# ST_LINK_V3E.net
KiCad netlist of a schematic drawn in Altium Designer
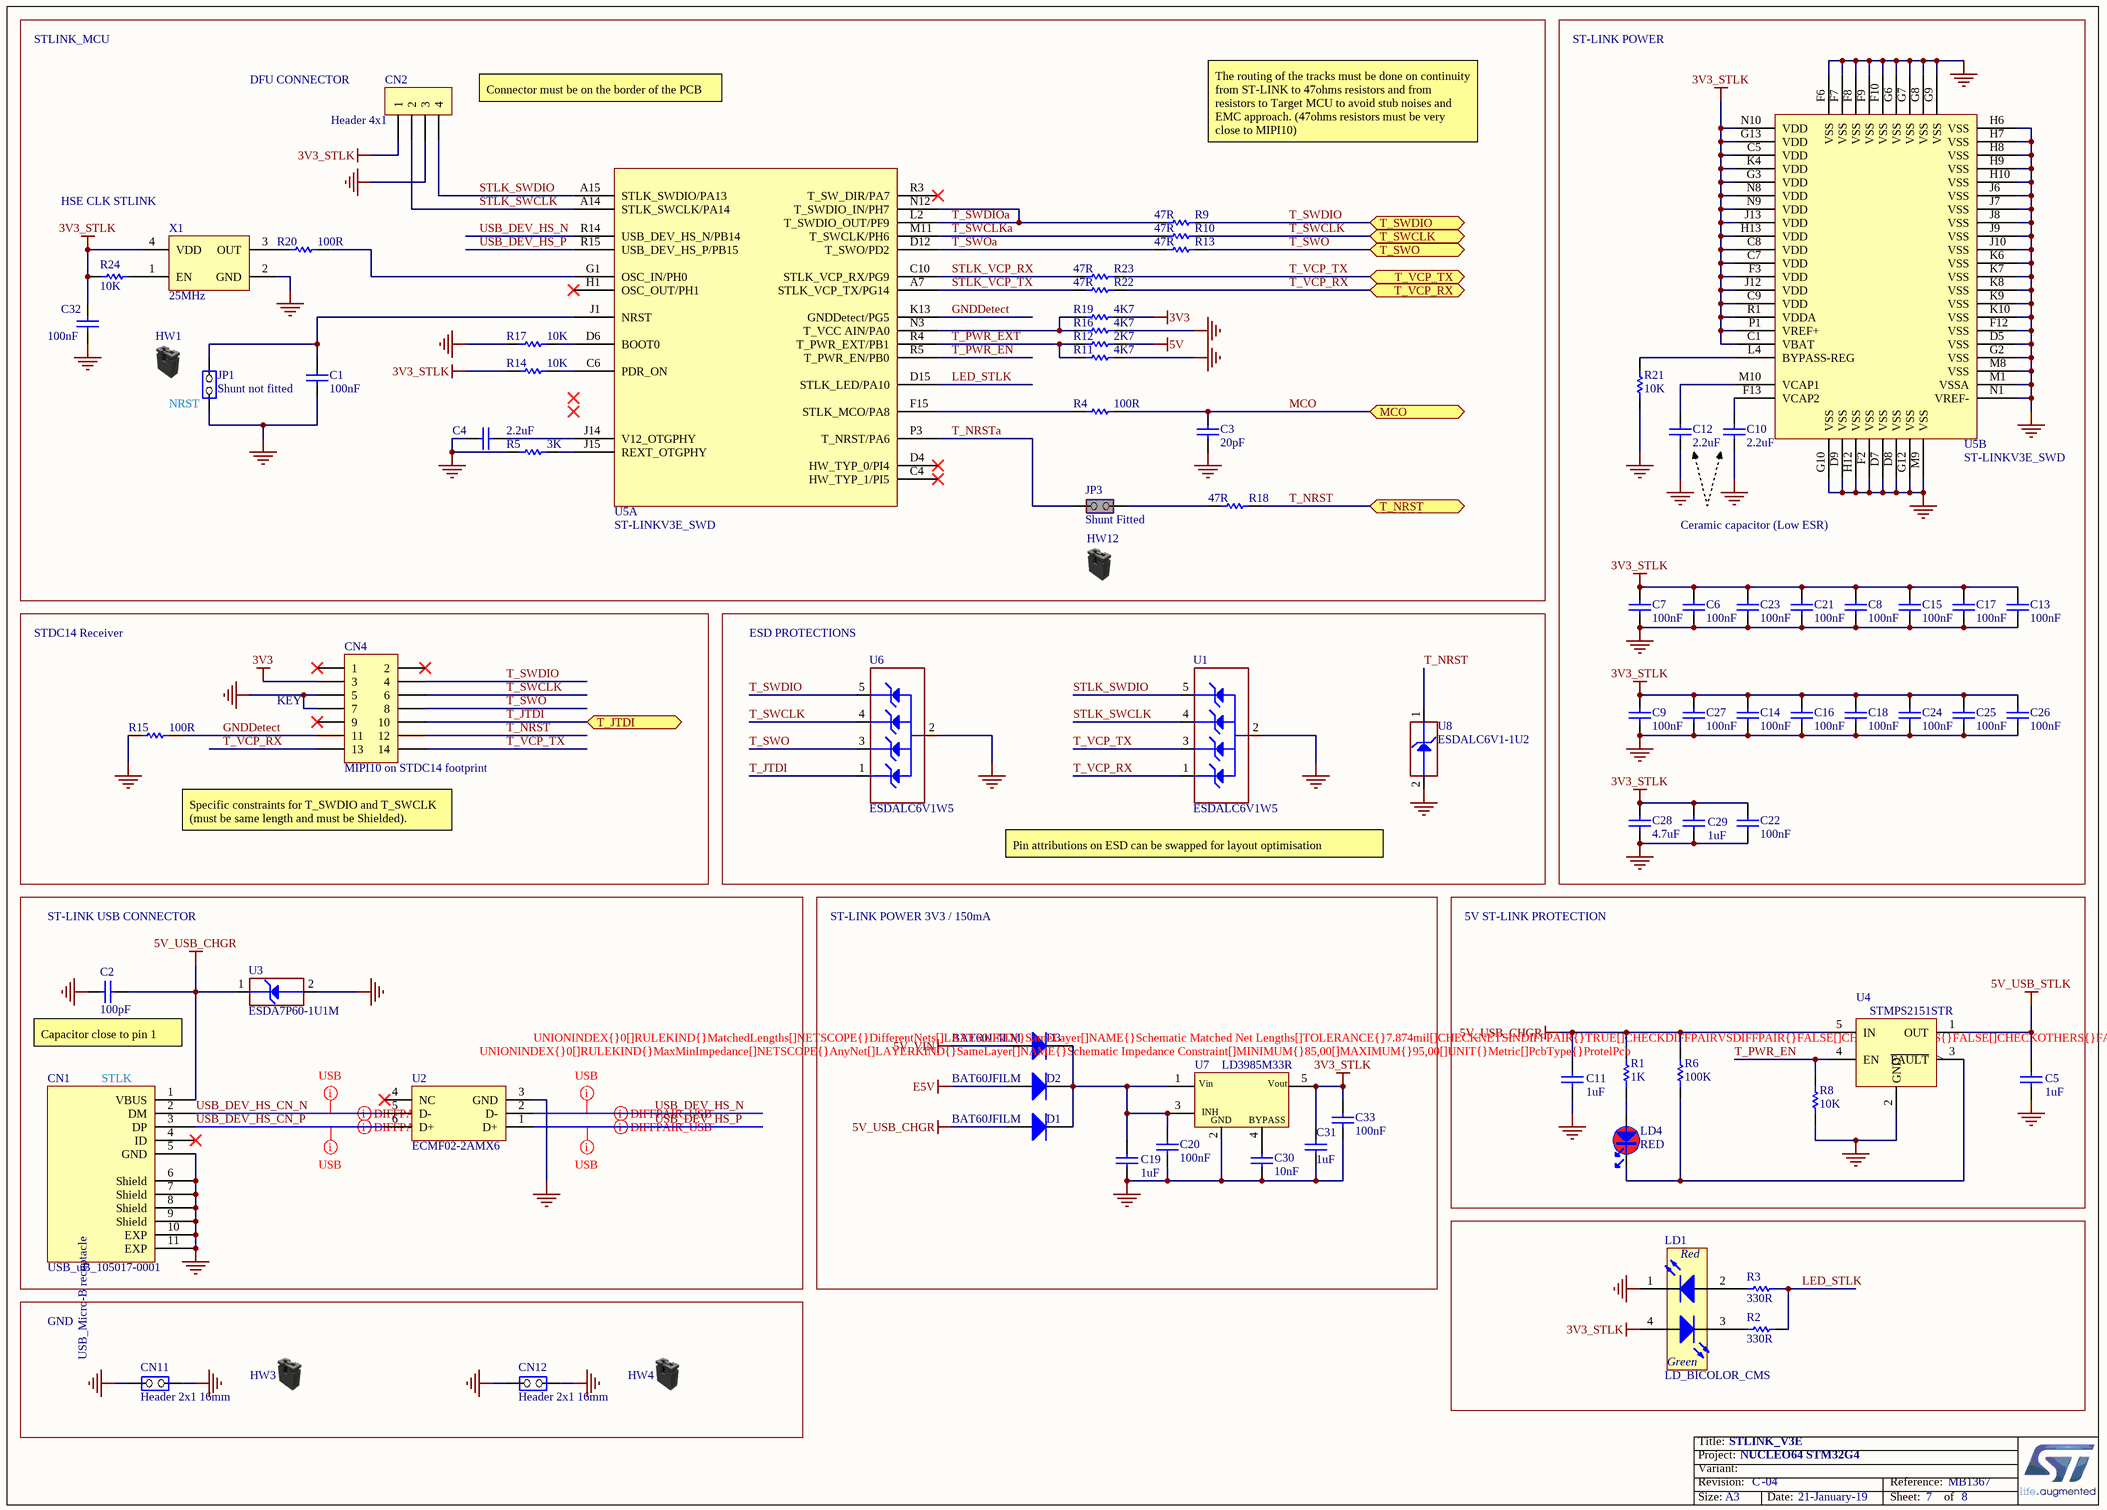
[diagram p0: ST_LINK_V3E.SchDoc]

(export (version "E")
  (design (tool "Eeschema 10.0.6"))
  (components
    (comp (ref "C1")
      (value "100nF")
      (footprint "C0402")
      (description "Capacitor, MLCC, 100nF, 16V, X7R, 10%, 0402, T=0,5mm")
      (fields
        (field (name "INTERNAL_PART_NUMBER") "MCD-00102")
        (field (name "MANUFACTURER_PART_NUMBER") "CC0402KRX7R7BB104")
      )
      (libsource (lib "MCD_PARTS_database") (part "Capacitor"))
    )
    (comp (ref "C2")
      (value "100pF")
      (footprint "C0402")
      (description "Capacitor, MLCC, 100pF, 50V, NPO, 5%, 0402, T=0,5mm")
      (fields
        (field (name "INTERNAL_PART_NUMBER") "MCD-00205")
        (field (name "MANUFACTURER_PART_NUMBER") "CC0402JRNPO9BN101")
      )
      (libsource (lib "MCD_PARTS_database") (part "Capacitor"))
    )
    (comp (ref "C3")
      (value "20pF")
      (footprint "C0402")
      (description "Capacitor, MLCC, 20pF, 50V, NPO, 5%, 0402, T=0,5mm")
      (fields
        (field (name "INTERNAL_PART_NUMBER") "MCD-00016")
        (field (name "MANUFACTURER_PART_NUMBER") "CC0402JRNPO9BN200")
      )
      (libsource (lib "MCD_PARTS_database") (part "Capacitor"))
    )
    (comp (ref "C4")
      (value "2.2uF")
      (footprint "C0603")
      (description "Capacitor, MLCC, 2.2uF, 10V, X5R, 10%, 0603, T=0,8mm")
      (fields
        (field (name "INTERNAL_PART_NUMBER") "MCD-00012")
        (field (name "MANUFACTURER_PART_NUMBER") "CC0603KRX5R6BB225")
      )
      (libsource (lib "MCD_PARTS_database") (part "Capacitor"))
    )
    (comp (ref "C5")
      (value "1uF")
      (footprint "C0603")
      (description "Capacitor, MLCC, 1uF, 16V, X5R, 10%, 0603, T=0,8mm")
      (fields
        (field (name "INTERNAL_PART_NUMBER") "MCD-00010")
        (field (name "MANUFACTURER_PART_NUMBER") "CC0603KRX5R7BB105")
      )
      (libsource (lib "MCD_PARTS_database") (part "Capacitor"))
    )
    (comp (ref "C6")
      (value "100nF")
      (footprint "C0402")
      (description "Capacitor, MLCC, 100nF, 16V, X7R, 10%, 0402, T=0,5mm")
      (fields
        (field (name "INTERNAL_PART_NUMBER") "MCD-00102")
        (field (name "MANUFACTURER_PART_NUMBER") "CC0402KRX7R7BB104")
      )
      (libsource (lib "MCD_PARTS_database") (part "Capacitor"))
    )
    (comp (ref "C7")
      (value "100nF")
      (footprint "C0402")
      (description "Capacitor, MLCC, 100nF, 16V, X7R, 10%, 0402, T=0,5mm")
      (fields
        (field (name "INTERNAL_PART_NUMBER") "MCD-00102")
        (field (name "MANUFACTURER_PART_NUMBER") "CC0402KRX7R7BB104")
      )
      (libsource (lib "MCD_PARTS_database") (part "Capacitor"))
    )
    (comp (ref "C8")
      (value "100nF")
      (footprint "C0402")
      (description "Capacitor, MLCC, 100nF, 16V, X7R, 10%, 0402, T=0,5mm")
      (fields
        (field (name "INTERNAL_PART_NUMBER") "MCD-00102")
        (field (name "MANUFACTURER_PART_NUMBER") "CC0402KRX7R7BB104")
      )
      (libsource (lib "MCD_PARTS_database") (part "Capacitor"))
    )
    (comp (ref "C9")
      (value "100nF")
      (footprint "C0402")
      (description "Capacitor, MLCC, 100nF, 16V, X7R, 10%, 0402, T=0,5mm")
      (fields
        (field (name "INTERNAL_PART_NUMBER") "MCD-00102")
        (field (name "MANUFACTURER_PART_NUMBER") "CC0402KRX7R7BB104")
      )
      (libsource (lib "MCD_PARTS_database") (part "Capacitor"))
    )
    (comp (ref "C10")
      (value "2.2uF")
      (footprint "C1206_H1P15")
      (description "Capacitor, MLCC, 2.2uF, 16V, X7R, 10%, 1206, T=1,15mm")
      (fields
        (field (name "INTERNAL_PART_NUMBER") "MCD-00008")
        (field (name "MANUFACTURER_PART_NUMBER") "CC1206KKX7R7BB225")
      )
      (libsource (lib "MCD_PARTS_database") (part "Capacitor"))
    )
    (comp (ref "C11")
      (value "1uF")
      (footprint "C0603")
      (description "Capacitor, MLCC, 1uF, 16V, X5R, 10%, 0603, T=0,8mm")
      (fields
        (field (name "INTERNAL_PART_NUMBER") "MCD-00010")
        (field (name "MANUFACTURER_PART_NUMBER") "CC0603KRX5R7BB105")
      )
      (libsource (lib "MCD_PARTS_database") (part "Capacitor"))
    )
    (comp (ref "C12")
      (value "2.2uF")
      (footprint "C1206_H1P15")
      (description "Capacitor, MLCC, 2.2uF, 16V, X7R, 10%, 1206, T=1,15mm")
      (fields
        (field (name "INTERNAL_PART_NUMBER") "MCD-00008")
        (field (name "MANUFACTURER_PART_NUMBER") "CC1206KKX7R7BB225")
      )
      (libsource (lib "MCD_PARTS_database") (part "Capacitor"))
    )
    (comp (ref "C13")
      (value "100nF")
      (footprint "C0402")
      (description "Capacitor, MLCC, 100nF, 16V, X7R, 10%, 0402, T=0,5mm")
      (fields
        (field (name "INTERNAL_PART_NUMBER") "MCD-00102")
        (field (name "MANUFACTURER_PART_NUMBER") "CC0402KRX7R7BB104")
      )
      (libsource (lib "MCD_PARTS_database") (part "Capacitor"))
    )
    (comp (ref "C14")
      (value "100nF")
      (footprint "C0402")
      (description "Capacitor, MLCC, 100nF, 16V, X7R, 10%, 0402, T=0,5mm")
      (fields
        (field (name "INTERNAL_PART_NUMBER") "MCD-00102")
        (field (name "MANUFACTURER_PART_NUMBER") "CC0402KRX7R7BB104")
      )
      (libsource (lib "MCD_PARTS_database") (part "Capacitor"))
    )
    (comp (ref "C15")
      (value "100nF")
      (footprint "C0402")
      (description "Capacitor, MLCC, 100nF, 16V, X7R, 10%, 0402, T=0,5mm")
      (fields
        (field (name "INTERNAL_PART_NUMBER") "MCD-00102")
        (field (name "MANUFACTURER_PART_NUMBER") "CC0402KRX7R7BB104")
      )
      (libsource (lib "MCD_PARTS_database") (part "Capacitor"))
    )
    (comp (ref "C16")
      (value "100nF")
      (footprint "C0402")
      (description "Capacitor, MLCC, 100nF, 16V, X7R, 10%, 0402, T=0,5mm")
      (fields
        (field (name "INTERNAL_PART_NUMBER") "MCD-00102")
        (field (name "MANUFACTURER_PART_NUMBER") "CC0402KRX7R7BB104")
      )
      (libsource (lib "MCD_PARTS_database") (part "Capacitor"))
    )
    (comp (ref "C17")
      (value "100nF")
      (footprint "C0402")
      (description "Capacitor, MLCC, 100nF, 16V, X7R, 10%, 0402, T=0,5mm")
      (fields
        (field (name "INTERNAL_PART_NUMBER") "MCD-00102")
        (field (name "MANUFACTURER_PART_NUMBER") "CC0402KRX7R7BB104")
      )
      (libsource (lib "MCD_PARTS_database") (part "Capacitor"))
    )
    (comp (ref "C18")
      (value "100nF")
      (footprint "C0402")
      (description "Capacitor, MLCC, 100nF, 16V, X7R, 10%, 0402, T=0,5mm")
      (fields
        (field (name "INTERNAL_PART_NUMBER") "MCD-00102")
        (field (name "MANUFACTURER_PART_NUMBER") "CC0402KRX7R7BB104")
      )
      (libsource (lib "MCD_PARTS_database") (part "Capacitor"))
    )
    (comp (ref "C19")
      (value "1uF")
      (footprint "C0603")
      (description "Capacitor, MLCC, 1uF, 16V, X5R, 10%, 0603, T=0,8mm")
      (fields
        (field (name "INTERNAL_PART_NUMBER") "MCD-00010")
        (field (name "MANUFACTURER_PART_NUMBER") "CC0603KRX5R7BB105")
      )
      (libsource (lib "MCD_PARTS_database") (part "Capacitor"))
    )
    (comp (ref "C20")
      (value "100nF")
      (footprint "C0402")
      (description "Capacitor, MLCC, 100nF, 16V, X7R, 10%, 0402, T=0,5mm")
      (fields
        (field (name "INTERNAL_PART_NUMBER") "MCD-00102")
        (field (name "MANUFACTURER_PART_NUMBER") "CC0402KRX7R7BB104")
      )
      (libsource (lib "MCD_PARTS_database") (part "Capacitor"))
    )
    (comp (ref "C21")
      (value "100nF")
      (footprint "C0402")
      (description "Capacitor, MLCC, 100nF, 16V, X7R, 10%, 0402, T=0,5mm")
      (fields
        (field (name "INTERNAL_PART_NUMBER") "MCD-00102")
        (field (name "MANUFACTURER_PART_NUMBER") "CC0402KRX7R7BB104")
      )
      (libsource (lib "MCD_PARTS_database") (part "Capacitor"))
    )
    (comp (ref "C22")
      (value "100nF")
      (footprint "C0402")
      (description "Capacitor, MLCC, 100nF, 16V, X7R, 10%, 0402, T=0,5mm")
      (fields
        (field (name "INTERNAL_PART_NUMBER") "MCD-00102")
        (field (name "MANUFACTURER_PART_NUMBER") "CC0402KRX7R7BB104")
      )
      (libsource (lib "MCD_PARTS_database") (part "Capacitor"))
    )
    (comp (ref "C23")
      (value "100nF")
      (footprint "C0402")
      (description "Capacitor, MLCC, 100nF, 16V, X7R, 10%, 0402, T=0,5mm")
      (fields
        (field (name "INTERNAL_PART_NUMBER") "MCD-00102")
        (field (name "MANUFACTURER_PART_NUMBER") "CC0402KRX7R7BB104")
      )
      (libsource (lib "MCD_PARTS_database") (part "Capacitor"))
    )
    (comp (ref "C24")
      (value "100nF")
      (footprint "C0402")
      (description "Capacitor, MLCC, 100nF, 16V, X7R, 10%, 0402, T=0,5mm")
      (fields
        (field (name "INTERNAL_PART_NUMBER") "MCD-00102")
        (field (name "MANUFACTURER_PART_NUMBER") "CC0402KRX7R7BB104")
      )
      (libsource (lib "MCD_PARTS_database") (part "Capacitor"))
    )
    (comp (ref "C25")
      (value "100nF")
      (footprint "C0402")
      (description "Capacitor, MLCC, 100nF, 16V, X7R, 10%, 0402, T=0,5mm")
      (fields
        (field (name "INTERNAL_PART_NUMBER") "MCD-00102")
        (field (name "MANUFACTURER_PART_NUMBER") "CC0402KRX7R7BB104")
      )
      (libsource (lib "MCD_PARTS_database") (part "Capacitor"))
    )
    (comp (ref "C26")
      (value "100nF")
      (footprint "C0402")
      (description "Capacitor, MLCC, 100nF, 16V, X7R, 10%, 0402, T=0,5mm")
      (fields
        (field (name "INTERNAL_PART_NUMBER") "MCD-00102")
        (field (name "MANUFACTURER_PART_NUMBER") "CC0402KRX7R7BB104")
      )
      (libsource (lib "MCD_PARTS_database") (part "Capacitor"))
    )
    (comp (ref "C27")
      (value "100nF")
      (footprint "C0402")
      (description "Capacitor, MLCC, 100nF, 16V, X7R, 10%, 0402, T=0,5mm")
      (fields
        (field (name "INTERNAL_PART_NUMBER") "MCD-00102")
        (field (name "MANUFACTURER_PART_NUMBER") "CC0402KRX7R7BB104")
      )
      (libsource (lib "MCD_PARTS_database") (part "Capacitor"))
    )
    (comp (ref "C28")
      (value "4.7uF")
      (footprint "C0603")
      (description "Capacitor, MLCC, 4.7uF, 16V, X5R, 10%, 0603, T=0.8mm")
      (fields
        (field (name "INTERNAL_PART_NUMBER") "MCD-00009")
        (field (name "MANUFACTURER_PART_NUMBER") "CC0603KRX5R7BB475")
      )
      (libsource (lib "MCD_PARTS_database") (part "Capacitor"))
    )
    (comp (ref "C29")
      (value "1uF")
      (footprint "C0603")
      (description "Capacitor, MLCC, 1uF, 16V, X5R, 10%, 0603, T=0,8mm")
      (fields
        (field (name "INTERNAL_PART_NUMBER") "MCD-00010")
        (field (name "MANUFACTURER_PART_NUMBER") "CC0603KRX5R7BB105")
      )
      (libsource (lib "MCD_PARTS_database") (part "Capacitor"))
    )
    (comp (ref "C30")
      (value "10nF")
      (footprint "C0402")
      (description "Capacitor, MLCC, 10nF, 16V, X7R, 10%, 0402, T=0.5mm")
      (fields
        (field (name "INTERNAL_PART_NUMBER") "MCD-00011")
        (field (name "MANUFACTURER_PART_NUMBER") "CC0402KRX7R7BB103")
      )
      (libsource (lib "MCD_PARTS_database") (part "Capacitor"))
    )
    (comp (ref "C31")
      (value "1uF")
      (footprint "C0603")
      (description "Capacitor, MLCC, 1uF, 16V, X5R, 10%, 0603, T=0,8mm")
      (fields
        (field (name "INTERNAL_PART_NUMBER") "MCD-00010")
        (field (name "MANUFACTURER_PART_NUMBER") "CC0603KRX5R7BB105")
      )
      (libsource (lib "MCD_PARTS_database") (part "Capacitor"))
    )
    (comp (ref "C32")
      (value "100nF")
      (footprint "C0402")
      (description "Capacitor, MLCC, 100nF, 16V, X7R, 10%, 0402, T=0,5mm")
      (fields
        (field (name "INTERNAL_PART_NUMBER") "MCD-00102")
        (field (name "MANUFACTURER_PART_NUMBER") "CC0402KRX7R7BB104")
      )
      (libsource (lib "MCD_PARTS_database") (part "Capacitor"))
    )
    (comp (ref "C33")
      (value "100nF")
      (footprint "C0402")
      (description "Capacitor, MLCC, 100nF, 16V, X7R, 10%, 0402, T=0,5mm")
      (fields
        (field (name "INTERNAL_PART_NUMBER") "MCD-00102")
        (field (name "MANUFACTURER_PART_NUMBER") "CC0402KRX7R7BB104")
      )
      (libsource (lib "MCD_PARTS_database") (part "Capacitor"))
    )
    (comp (ref "CN1")
      (value "USB_uB_105017-0001")
      (footprint "CON_USBMICROB_MOLEX_105017-0001_H2P90")
      (description "USB-MICRO-B, 0.65mm, RA, SMT, Bottom Mount,")
      (fields
        (field (name "INTERNAL_PART_NUMBER") "MCD-00028")
        (field (name "MANUFACTURER_PART_NUMBER") "1050170001")
      )
      (libsource (lib "MCD_PARTS_database") (part "USB_uB_105017.0001"))
    )
    (comp (ref "CN2")
      (value "Header 4x1")
      (footprint "CON_SAMTEC_TSW-104-07-G-S")
      (description "Header, 4x1, 2,54mm, VR, TH, Height 5.84mm/2.54mm")
      (fields
        (field (name "INTERNAL_PART_NUMBER") "MCD-00029")
        (field (name "MANUFACTURER_PART_NUMBER") "TSW-104-07-x-S")
      )
      (libsource (lib "MCD_PARTS_database") (part "Header 4x1"))
    )
    (comp (ref "CN4")
      (value "MIPI10 on STDC14 footprint")
      (footprint "CON_STDC14_Receiver_MEDIUM_WITH_MIPI10_3D")
      (fields
        (field (name "INTERNAL_PART_NUMBER") "MCD-01226")
        (field (name "MANUFACTURER_PART_NUMBER") "FTSH-105-01-L-DV-K")
        (field (name "MANUFACTURER") "SAMTEC")
      )
      (libsource (lib "MCD_PARTS_database") (part "Header 7x2"))
    )
    (comp (ref "CN11")
      (value "Header 2x1 16mm")
      (footprint "CON_SAMTEC_TSW-102-09-X-S")
      (description "Header, 2x1, 2,54mm, VR, TH, Height 5.84mm/10.16mm")
      (fields
        (field (name "INTERNAL_PART_NUMBER") "MCD-00214")
        (field (name "MANUFACTURER_PART_NUMBER") "TSW-102-09-x-S")
      )
      (libsource (lib "MCD_PARTS_database") (part "Jumper_Header 2x1"))
    )
    (comp (ref "CN12")
      (value "Header 2x1 16mm")
      (footprint "CON_SAMTEC_TSW-102-09-X-S")
      (description "Header, 2x1, 2,54mm, VR, TH, Height 5.84mm/10.16mm")
      (fields
        (field (name "INTERNAL_PART_NUMBER") "MCD-00214")
        (field (name "MANUFACTURER_PART_NUMBER") "TSW-102-09-x-S")
      )
      (libsource (lib "MCD_PARTS_database") (part "Jumper_Header 2x1"))
    )
    (comp (ref "D1")
      (value "BAT60JFILM")
      (footprint "DIO_SOD323")
      (fields
        (field (name "INTERNAL_PART_NUMBER") "MCD-00034")
        (field (name "MANUFACTURER") "STMICROELECTRONICS")
      )
      (libsource (lib "MCD_PARTS_database") (part "BAT60JFILM"))
    )
    (comp (ref "D2")
      (value "BAT60JFILM")
      (footprint "DIO_SOD323")
      (fields
        (field (name "INTERNAL_PART_NUMBER") "MCD-00034")
        (field (name "MANUFACTURER") "STMICROELECTRONICS")
      )
      (libsource (lib "MCD_PARTS_database") (part "BAT60JFILM"))
    )
    (comp (ref "D3")
      (value "BAT60JFILM")
      (footprint "DIO_SOD323")
      (fields
        (field (name "INTERNAL_PART_NUMBER") "MCD-00034")
        (field (name "MANUFACTURER") "STMICROELECTRONICS")
      )
      (libsource (lib "MCD_PARTS_database") (part "BAT60JFILM"))
    )
    (comp (ref "HW1")
      (value "~")
      (description "SHUNT 2.54mm BLACK")
      (fields
        (field (name "INTERNAL_PART_NUMBER") "MCD-00043")
        (field (name "MANUFACTURER_PART_NUMBER") "SNT-100-BK-G")
      )
      (libsource (lib "MCD_PARTS_database") (part "Shunt Black 2.54mm"))
    )
    (comp (ref "HW3")
      (value "~")
      (description "SHUNT 2.54mm BLACK")
      (fields
        (field (name "INTERNAL_PART_NUMBER") "MCD-00043")
        (field (name "MANUFACTURER_PART_NUMBER") "SNT-100-BK-G")
      )
      (libsource (lib "MCD_PARTS_database") (part "Shunt Black 2.54mm"))
    )
    (comp (ref "HW4")
      (value "~")
      (description "SHUNT 2.54mm BLACK")
      (fields
        (field (name "INTERNAL_PART_NUMBER") "MCD-00043")
        (field (name "MANUFACTURER_PART_NUMBER") "SNT-100-BK-G")
      )
      (libsource (lib "MCD_PARTS_database") (part "Shunt Black 2.54mm"))
    )
    (comp (ref "HW12")
      (value "~")
      (description "SHUNT 2.54mm BLACK")
      (fields
        (field (name "INTERNAL_PART_NUMBER") "MCD-00043")
        (field (name "MANUFACTURER_PART_NUMBER") "SNT-100-BK-G")
      )
      (libsource (lib "MCD_PARTS_database") (part "Shunt Black 2.54mm"))
    )
    (comp (ref "JP1")
      (value "Shunt not fitted")
      (footprint "CON_SAMTEC_TSW-102-07-G-S")
      (description "Header, 2x1, 2,54mm, VR, TH, Height 5.84mm/2.54mm")
      (fields
        (field (name "INTERNAL_PART_NUMBER") "MCD-00045")
        (field (name "MANUFACTURER_PART_NUMBER") "TSW-102-07-x-S")
      )
      (libsource (lib "MCD_PARTS_database") (part "Jumper_Header 2x1"))
    )
    (comp (ref "JP3")
      (value "Shunt Fitted")
      (footprint "CON_SAMTEC_TSW-102-07-G-S")
      (description "Header, 2x1, 2,54mm, VR, TH, Height 5.84mm/2.54mm - Shunt Fitted by default")
      (fields
        (field (name "INTERNAL_PART_NUMBER") "MCD-00683")
        (field (name "MANUFACTURER_PART_NUMBER") "TSW-102-07-x-S")
      )
      (libsource (lib "MCD_PARTS_database") (part "Jumper_Header 2x1 Fitted"))
    )
    (comp (ref "LD1")
      (value "LD_BICOLOR_CMS")
      (footprint "LED_BI-GR_HSMF-A201-A00J1")
      (description "LED Bicolor")
      (fields
        (field (name "INTERNAL_PART_NUMBER") "MCD-00051")
        (field (name "MANUFACTURER_PART_NUMBER") "HSMF-A201-A00J1")
      )
      (libsource (lib "MCD_PARTS_database") (part "LD_BICOLOR_CMS"))
    )
    (comp (ref "LD4")
      (value "RED")
      (footprint "LED_0603_RED")
      (description "LED, Red, 0603")
      (fields
        (field (name "INTERNAL_PART_NUMBER") "MCD-00049")
        (field (name "MANUFACTURER_PART_NUMBER") "19-213-R6C-AP1Q2B/3T")
      )
      (libsource (lib "MCD_PARTS_database") (part "LED_red"))
    )
    (comp (ref "R1")
      (value "1K")
      (footprint "R0603")
      (description "Resistor,1K,0603,1%,1/10W")
      (fields
        (field (name "INTERNAL_PART_NUMBER") "MCD-00070")
        (field (name "MANUFACTURER_PART_NUMBER") "RC0603FR-071KL")
      )
      (libsource (lib "MCD_PARTS_database") (part "Resistor"))
    )
    (comp (ref "R2")
      (value "330R")
      (footprint "R0603")
      (description "Resistor,330R,0603,1%,1/10W")
      (fields
        (field (name "INTERNAL_PART_NUMBER") "MCD-00197")
        (field (name "MANUFACTURER_PART_NUMBER") "RC0603FR-07330RL")
      )
      (libsource (lib "MCD_PARTS_database") (part "Resistor"))
    )
    (comp (ref "R3")
      (value "330R")
      (footprint "R0603")
      (description "Resistor,330R,0603,1%,1/10W")
      (fields
        (field (name "INTERNAL_PART_NUMBER") "MCD-00197")
        (field (name "MANUFACTURER_PART_NUMBER") "RC0603FR-07330RL")
      )
      (libsource (lib "MCD_PARTS_database") (part "Resistor"))
    )
    (comp (ref "R4")
      (value "100R")
      (footprint "R0402")
      (description "Resistor,100R,0402,1%,1/16W")
      (fields
        (field (name "INTERNAL_PART_NUMBER") "MCD-00119")
        (field (name "MANUFACTURER_PART_NUMBER") "RC0402FR-07100RL")
      )
      (libsource (lib "MCD_PARTS_database") (part "Resistor"))
    )
    (comp (ref "R5")
      (value "3K")
      (footprint "R0402")
      (description "Resistor,3K,0402,1%,1/16W")
      (fields
        (field (name "INTERNAL_PART_NUMBER") "MCD-00185")
        (field (name "MANUFACTURER_PART_NUMBER") "RC0402FR-073KL")
      )
      (libsource (lib "MCD_PARTS_database") (part "Resistor"))
    )
    (comp (ref "R6")
      (value "100K")
      (footprint "R0603")
      (description "Resistor,100K,0603,1%,1/10W")
      (fields
        (field (name "INTERNAL_PART_NUMBER") "MCD-00223")
        (field (name "MANUFACTURER_PART_NUMBER") "RC0603FR-07100KL")
      )
      (libsource (lib "MCD_PARTS_database") (part "Resistor"))
    )
    (comp (ref "R8")
      (value "10K")
      (footprint "R0603")
      (description "Resistor,10K,0603,1%,1/10W")
      (fields
        (field (name "INTERNAL_PART_NUMBER") "MCD-00220")
        (field (name "MANUFACTURER_PART_NUMBER") "RC0603FR-0710KL")
      )
      (libsource (lib "MCD_PARTS_database") (part "Resistor"))
    )
    (comp (ref "R9")
      (value "47R")
      (footprint "R0402")
      (description "Resistor,47R,0402,1%,1/16W")
      (fields
        (field (name "INTERNAL_PART_NUMBER") "MCD-00481")
        (field (name "MANUFACTURER_PART_NUMBER") "RC0402FR-0747RL")
      )
      (libsource (lib "MCD_PARTS_database") (part "Resistor"))
    )
    (comp (ref "R10")
      (value "47R")
      (footprint "R0402")
      (description "Resistor,47R,0402,1%,1/16W")
      (fields
        (field (name "INTERNAL_PART_NUMBER") "MCD-00481")
        (field (name "MANUFACTURER_PART_NUMBER") "RC0402FR-0747RL")
      )
      (libsource (lib "MCD_PARTS_database") (part "Resistor"))
    )
    (comp (ref "R11")
      (value "4K7")
      (footprint "R0402")
      (description "Resistor,4K7,0402,1%,1/16W")
      (fields
        (field (name "INTERNAL_PART_NUMBER") "MCD-00065")
        (field (name "MANUFACTURER_PART_NUMBER") "RC0402FR-074K7L")
      )
      (libsource (lib "MCD_PARTS_database") (part "Resistor"))
    )
    (comp (ref "R12")
      (value "2K7")
      (footprint "R0402")
      (description "Resistor,2K7,0402,1%,1/16W")
      (fields
        (field (name "INTERNAL_PART_NUMBER") "MCD-00055")
        (field (name "MANUFACTURER_PART_NUMBER") "RC0402FR-072K7L")
      )
      (libsource (lib "MCD_PARTS_database") (part "Resistor"))
    )
    (comp (ref "R13")
      (value "47R")
      (footprint "R0402")
      (description "Resistor,47R,0402,1%,1/16W")
      (fields
        (field (name "INTERNAL_PART_NUMBER") "MCD-00481")
        (field (name "MANUFACTURER_PART_NUMBER") "RC0402FR-0747RL")
      )
      (libsource (lib "MCD_PARTS_database") (part "Resistor"))
    )
    (comp (ref "R14")
      (value "10K")
      (footprint "R0402")
      (description "Resistor,10K,0402,1%,1/16W")
      (fields
        (field (name "INTERNAL_PART_NUMBER") "MCD-00053")
        (field (name "MANUFACTURER_PART_NUMBER") "RC0402FR-0710KL")
      )
      (libsource (lib "MCD_PARTS_database") (part "Resistor"))
    )
    (comp (ref "R15")
      (value "100R")
      (footprint "R0402")
      (description "Resistor,100R,0402,1%,1/16W")
      (fields
        (field (name "INTERNAL_PART_NUMBER") "MCD-00119")
        (field (name "MANUFACTURER_PART_NUMBER") "RC0402FR-07100RL")
      )
      (libsource (lib "MCD_PARTS_database") (part "Resistor"))
    )
    (comp (ref "R16")
      (value "4K7")
      (footprint "R0402")
      (description "Resistor,4K7,0402,1%,1/16W")
      (fields
        (field (name "INTERNAL_PART_NUMBER") "MCD-00065")
        (field (name "MANUFACTURER_PART_NUMBER") "RC0402FR-074K7L")
      )
      (libsource (lib "MCD_PARTS_database") (part "Resistor"))
    )
    (comp (ref "R17")
      (value "10K")
      (footprint "R0402")
      (description "Resistor,10K,0402,1%,1/16W")
      (fields
        (field (name "INTERNAL_PART_NUMBER") "MCD-00053")
        (field (name "MANUFACTURER_PART_NUMBER") "RC0402FR-0710KL")
      )
      (libsource (lib "MCD_PARTS_database") (part "Resistor"))
    )
    (comp (ref "R18")
      (value "47R")
      (footprint "R0402")
      (description "Resistor,47R,0402,1%,1/16W")
      (fields
        (field (name "INTERNAL_PART_NUMBER") "MCD-00481")
        (field (name "MANUFACTURER_PART_NUMBER") "RC0402FR-0747RL")
      )
      (libsource (lib "MCD_PARTS_database") (part "Resistor"))
    )
    (comp (ref "R19")
      (value "4K7")
      (footprint "R0402")
      (description "Resistor,4K7,0402,1%,1/16W")
      (fields
        (field (name "INTERNAL_PART_NUMBER") "MCD-00065")
        (field (name "MANUFACTURER_PART_NUMBER") "RC0402FR-074K7L")
      )
      (libsource (lib "MCD_PARTS_database") (part "Resistor"))
    )
    (comp (ref "R20")
      (value "100R")
      (footprint "R0402")
      (description "Resistor,100R,0402,1%,1/16W")
      (fields
        (field (name "INTERNAL_PART_NUMBER") "MCD-00119")
        (field (name "MANUFACTURER_PART_NUMBER") "RC0402FR-07100RL")
      )
      (libsource (lib "MCD_PARTS_database") (part "Resistor"))
    )
    (comp (ref "R21")
      (value "10K")
      (footprint "R0402")
      (description "Resistor,10K,0402,1%,1/16W")
      (fields
        (field (name "INTERNAL_PART_NUMBER") "MCD-00053")
        (field (name "MANUFACTURER_PART_NUMBER") "RC0402FR-0710KL")
      )
      (libsource (lib "MCD_PARTS_database") (part "Resistor"))
    )
    (comp (ref "R22")
      (value "47R")
      (footprint "R0402")
      (description "Resistor,47R,0402,1%,1/16W")
      (fields
        (field (name "INTERNAL_PART_NUMBER") "MCD-00481")
        (field (name "MANUFACTURER_PART_NUMBER") "RC0402FR-0747RL")
      )
      (libsource (lib "MCD_PARTS_database") (part "Resistor"))
    )
    (comp (ref "R23")
      (value "47R")
      (footprint "R0402")
      (description "Resistor,47R,0402,1%,1/16W")
      (fields
        (field (name "INTERNAL_PART_NUMBER") "MCD-00481")
        (field (name "MANUFACTURER_PART_NUMBER") "RC0402FR-0747RL")
      )
      (libsource (lib "MCD_PARTS_database") (part "Resistor"))
    )
    (comp (ref "R24")
      (value "10K")
      (footprint "R0402")
      (description "Resistor,10K,0402,1%,1/16W")
      (fields
        (field (name "INTERNAL_PART_NUMBER") "MCD-00053")
        (field (name "MANUFACTURER_PART_NUMBER") "RC0402FR-0710KL")
      )
      (libsource (lib "MCD_PARTS_database") (part "Resistor"))
    )
    (comp (ref "U1")
      (value "ESDALC6V1W5")
      (footprint "ESD_SOT323-5L")
      (description "Dual Transil array for ESD protection")
      (fields
        (field (name "INTERNAL_PART_NUMBER") "MCD-00136")
        (field (name "MANUFACTURER") "STMICROELECTRONICS")
      )
      (libsource (lib "MCD_PARTS_database") (part "ESDALC6V1W5"))
    )
    (comp (ref "U2")
      (value "ECMF02-2AMX6")
      (footprint "ESD_QFN-6L_1P7X1P5_P050")
      (description "Common mode filter with ESD protection for USB 2.0 interface")
      (fields
        (field (name "INTERNAL_PART_NUMBER") "MCD-00649")
        (field (name "MANUFACTURER") "STMICROELECTRONICS")
      )
      (libsource (lib "MCD_PARTS_database") (part "ECMF02-2AMX6"))
    )
    (comp (ref "U3")
      (value "ESDA7P60-1U1M")
      (footprint "ESD_QFN2_1P6X1_P125")
      (description "High power transient voltage suppressor, 7V breakdown")
      (fields
        (field (name "INTERNAL_PART_NUMBER") "MCD-00251")
        (field (name "MANUFACTURER") "STMICROELECTRONICS")
      )
      (libsource (lib "MCD_PARTS_database") (part "ESD-TRANSIL"))
    )
    (comp (ref "U4")
      (value "STMPS2151STR")
      (footprint "MOS_SOT23-5L")
      (description "500mA, Enhanced single channel power switches with active high enable pin")
      (fields
        (field (name "INTERNAL_PART_NUMBER") "MCD-00159")
        (field (name "MANUFACTURER") "STMICROELECTRONICS")
      )
      (libsource (lib "MCD_PARTS_database") (part "STMPS2151STR"))
    )
    (comp (ref "U5")
      (value "ST-LINKV3E_SWD")
      (footprint "ICC_UFBGA201_176+25_10X10_P065")
      (description "STM32F723IEK  (STM32F7) BGA176")
      (fields
        (field (name "INTERNAL_PART_NUMBER") "MCD-00596")
        (field (name "MANUFACTURER_PART_NUMBER") "STM32F723IEK6")
      )
      (libsource (lib "MCD_PARTS_database") (part "ST-LINKV3E_SWD"))
    )
    (comp (ref "U6")
      (value "ESDALC6V1W5")
      (footprint "ESD_SOT323-5L")
      (description "Dual Transil array for ESD protection")
      (fields
        (field (name "INTERNAL_PART_NUMBER") "MCD-00136")
        (field (name "MANUFACTURER") "STMICROELECTRONICS")
      )
      (libsource (lib "MCD_PARTS_database") (part "ESDALC6V1W5"))
    )
    (comp (ref "U7")
      (value "LD3985M33R")
      (footprint "REG_SOT23-5L")
      (description "Ultra low drop-low noise BiCMOS voltage, regulators low ESR capacitors compatible")
      (fields
        (field (name "INTERNAL_PART_NUMBER") "MCD-00086")
        (field (name "MANUFACTURER") "STMICROELECTRONICS")
      )
      (libsource (lib "MCD_PARTS_database") (part "LD3985M33R"))
    )
    (comp (ref "U8")
      (value "ESDALC6V1-1U2")
      (footprint "ESD_ST0201")
      (description "ESD protection 6V1")
      (fields
        (field (name "INTERNAL_PART_NUMBER") "MCD-00170")
        (field (name "MANUFACTURER") "STMICROELECTRONICS")
      )
      (libsource (lib "") (part "ESD-TRANSIL_1"))
    )
    (comp (ref "X1")
      (value "25MHz")
      (footprint "OSC_NDK_NZ2520SB_4P")
      (description "Oscillator 25.00Mhz, -+50PPM, 3.3V, Temp -55 to +125°C")
      (fields
        (field (name "INTERNAL_PART_NUMBER") "MCD-00597")
        (field (name "MANUFACTURER_PART_NUMBER") "NZ2520SB 25MHz END4869B")
      )
      (libsource (lib "MCD_PARTS_database") (part "Oscillator_4pins"))
    )
  )
  (nets
    (net (code "1") (name "/GNDDetect") (class "Default")
      (node (ref "CN4") (pin "11") (pinfunction "11_11") (pintype "passive"))
      (node (ref "R15") (pin "2") (pinfunction "2_2") (pintype "passive"))
      (node (ref "U5") (pin "K13") (pinfunction "GNDDetect/PG5_K13") (pintype "passive"))
    )
    (net (code "2") (name "/LED_STLK") (class "Default")
      (node (ref "R2") (pin "2") (pinfunction "2_2") (pintype "passive"))
      (node (ref "R3") (pin "2") (pinfunction "2_2") (pintype "passive"))
      (node (ref "U5") (pin "D15") (pinfunction "STLK_LED/PA10_D15") (pintype "passive"))
    )
    (net (code "3") (name "/MCO") (class "Default")
      (node (ref "C3") (pin "2") (pinfunction "2_2") (pintype "passive"))
      (node (ref "R4") (pin "2") (pinfunction "2_2") (pintype "passive"))
    )
    (net (code "4") (name "/STLK_SWCLK") (class "Default")
      (node (ref "CN2") (pin "2") (pinfunction "2_2") (pintype "passive"))
      (node (ref "U1") (pin "4") (pinfunction "IO3_4") (pintype "passive"))
      (node (ref "U5") (pin "A14") (pinfunction "STLK_SWCLK/PA14_A14") (pintype "passive"))
    )
    (net (code "5") (name "/STLK_SWDIO") (class "Default")
      (node (ref "CN2") (pin "4") (pinfunction "4_4") (pintype "passive"))
      (node (ref "U1") (pin "5") (pinfunction "IO4_5") (pintype "passive"))
      (node (ref "U5") (pin "A15") (pinfunction "STLK_SWDIO/PA13_A15") (pintype "passive"))
    )
    (net (code "6") (name "/STLK_VCP_RX") (class "Default")
      (node (ref "R23") (pin "1") (pinfunction "1_1") (pintype "passive"))
      (node (ref "U5") (pin "C10") (pinfunction "STLK_VCP_RX/PG9_C10") (pintype "passive"))
    )
    (net (code "7") (name "/STLK_VCP_TX") (class "Default")
      (node (ref "R22") (pin "1") (pinfunction "1_1") (pintype "passive"))
      (node (ref "U5") (pin "A7") (pinfunction "STLK_VCP_TX/PG14_A7") (pintype "passive"))
    )
    (net (code "8") (name "/T_JTDI") (class "Default")
      (node (ref "CN4") (pin "10") (pinfunction "10_10") (pintype "passive"))
      (node (ref "U6") (pin "1") (pinfunction "IO1_1") (pintype "passive"))
    )
    (net (code "9") (name "/T_NRST") (class "Default")
      (node (ref "CN4") (pin "12") (pinfunction "12_12") (pintype "passive"))
      (node (ref "R18") (pin "2") (pinfunction "2_2") (pintype "passive"))
      (node (ref "U8") (pin "1") (pinfunction "IO1_1") (pintype "passive"))
    )
    (net (code "10") (name "/T_NRSTa") (class "Default")
      (node (ref "JP3") (pin "1") (pinfunction "COMMON_1") (pintype "passive"))
      (node (ref "U5") (pin "P3") (pinfunction "T_NRST/PA6_P3") (pintype "passive"))
    )
    (net (code "11") (name "/T_PWR_EN") (class "Default")
      (node (ref "R8") (pin "1") (pinfunction "1_1") (pintype "passive"))
      (node (ref "U4") (pin "4") (pinfunction "EN_4") (pintype "passive"))
      (node (ref "U5") (pin "R5") (pinfunction "T_PWR_EN/PB0_R5") (pintype "passive"))
    )
    (net (code "12") (name "/T_PWR_EXT") (class "Default")
      (node (ref "R11") (pin "2") (pinfunction "2_2") (pintype "passive"))
      (node (ref "R12") (pin "2") (pinfunction "2_2") (pintype "passive"))
      (node (ref "U5") (pin "R4") (pinfunction "T_PWR_EXT/PB1_R4") (pintype "passive"))
    )
    (net (code "13") (name "/T_SWCLK") (class "Default")
      (node (ref "CN4") (pin "6") (pinfunction "6_6") (pintype "passive"))
      (node (ref "R10") (pin "2") (pinfunction "2_2") (pintype "passive"))
      (node (ref "U6") (pin "4") (pinfunction "IO3_4") (pintype "passive"))
    )
    (net (code "14") (name "/T_SWCLKa") (class "Default")
      (node (ref "R10") (pin "1") (pinfunction "1_1") (pintype "passive"))
      (node (ref "U5") (pin "M11") (pinfunction "T_SWCLK/PH6_M11") (pintype "passive"))
    )
    (net (code "15") (name "/T_SWDIO") (class "Default")
      (node (ref "CN4") (pin "4") (pinfunction "4_4") (pintype "passive"))
      (node (ref "R9") (pin "2") (pinfunction "2_2") (pintype "passive"))
      (node (ref "U6") (pin "5") (pinfunction "IO4_5") (pintype "passive"))
    )
    (net (code "16") (name "/T_SWDIOa") (class "Default")
      (node (ref "R9") (pin "1") (pinfunction "1_1") (pintype "passive"))
      (node (ref "U5") (pin "L2") (pinfunction "T_SWDIO_OUT/PF9_L2") (pintype "passive"))
      (node (ref "U5") (pin "N12") (pinfunction "T_SWDIO_IN/PH7_N12") (pintype "passive"))
    )
    (net (code "17") (name "/T_SWO") (class "Default")
      (node (ref "CN4") (pin "8") (pinfunction "8_8") (pintype "passive"))
      (node (ref "R13") (pin "2") (pinfunction "2_2") (pintype "passive"))
      (node (ref "U6") (pin "3") (pinfunction "IO2_3") (pintype "passive"))
    )
    (net (code "18") (name "/T_SWOa") (class "Default")
      (node (ref "R13") (pin "1") (pinfunction "1_1") (pintype "passive"))
      (node (ref "U5") (pin "D12") (pinfunction "T_SWO/PD2_D12") (pintype "passive"))
    )
    (net (code "19") (name "/T_VCP_RX") (class "Default")
      (node (ref "CN4") (pin "13") (pinfunction "13_13") (pintype "passive"))
      (node (ref "R22") (pin "2") (pinfunction "2_2") (pintype "passive"))
      (node (ref "U1") (pin "1") (pinfunction "IO1_1") (pintype "passive"))
    )
    (net (code "20") (name "/T_VCP_TX") (class "Default")
      (node (ref "CN4") (pin "14") (pinfunction "14_14") (pintype "passive"))
      (node (ref "R23") (pin "2") (pinfunction "2_2") (pintype "passive"))
      (node (ref "U1") (pin "3") (pinfunction "IO2_3") (pintype "passive"))
    )
    (net (code "21") (name "/USB_DEV_HS_CN_N") (class "Default")
      (node (ref "CN1") (pin "2") (pinfunction "DM_2") (pintype "passive"))
      (node (ref "U2") (pin "5") (pinfunction "D-_5") (pintype "passive"))
    )
    (net (code "22") (name "/USB_DEV_HS_CN_P") (class "Default")
      (node (ref "CN1") (pin "3") (pinfunction "DP_3") (pintype "passive"))
      (node (ref "U2") (pin "6") (pinfunction "D+_6") (pintype "passive"))
    )
    (net (code "23") (name "/USB_DEV_HS_N") (class "Default")
      (node (ref "U2") (pin "2") (pinfunction "D-_2") (pintype "passive"))
      (node (ref "U5") (pin "R14") (pinfunction "USB_DEV_HS_N/PB14_R14") (pintype "passive"))
    )
    (net (code "24") (name "/USB_DEV_HS_P") (class "Default")
      (node (ref "U2") (pin "1") (pinfunction "D+_1") (pintype "passive"))
      (node (ref "U5") (pin "R15") (pinfunction "USB_DEV_HS_P/PB15_R15") (pintype "passive"))
    )
    (net (code "25") (name "3V3") (class "Default")
      (node (ref "CN4") (pin "3") (pinfunction "3_3") (pintype "passive"))
      (node (ref "R19") (pin "2") (pinfunction "2_2") (pintype "passive"))
    )
    (net (code "26") (name "3V3_STLK") (class "Default")
      (node (ref "C13") (pin "2") (pinfunction "2_2") (pintype "passive"))
      (node (ref "C14") (pin "2") (pinfunction "2_2") (pintype "passive"))
      (node (ref "C15") (pin "2") (pinfunction "2_2") (pintype "passive"))
      (node (ref "C16") (pin "2") (pinfunction "2_2") (pintype "passive"))
      (node (ref "C17") (pin "2") (pinfunction "2_2") (pintype "passive"))
      (node (ref "C18") (pin "2") (pinfunction "2_2") (pintype "passive"))
      (node (ref "C21") (pin "2") (pinfunction "2_2") (pintype "passive"))
      (node (ref "C22") (pin "2") (pinfunction "2_2") (pintype "passive"))
      (node (ref "C23") (pin "2") (pinfunction "2_2") (pintype "passive"))
      (node (ref "C24") (pin "2") (pinfunction "2_2") (pintype "passive"))
      (node (ref "C25") (pin "2") (pinfunction "2_2") (pintype "passive"))
      (node (ref "C26") (pin "2") (pinfunction "2_2") (pintype "passive"))
      (node (ref "C27") (pin "2") (pinfunction "2_2") (pintype "passive"))
      (node (ref "C28") (pin "2") (pinfunction "2_2") (pintype "passive"))
      (node (ref "C29") (pin "2") (pinfunction "2_2") (pintype "passive"))
      (node (ref "C31") (pin "2") (pinfunction "2_2") (pintype "passive"))
      (node (ref "C32") (pin "2") (pinfunction "2_2") (pintype "passive"))
      (node (ref "C33") (pin "2") (pinfunction "2_2") (pintype "passive"))
      (node (ref "C6") (pin "2") (pinfunction "2_2") (pintype "passive"))
      (node (ref "C7") (pin "2") (pinfunction "2_2") (pintype "passive"))
      (node (ref "C8") (pin "2") (pinfunction "2_2") (pintype "passive"))
      (node (ref "C9") (pin "2") (pinfunction "2_2") (pintype "passive"))
      (node (ref "CN2") (pin "1") (pinfunction "1_1") (pintype "passive"))
      (node (ref "LD1") (pin "4") (pinfunction "YellowGreen_anode_4") (pintype "passive"))
      (node (ref "R14") (pin "1") (pinfunction "1_1") (pintype "passive"))
      (node (ref "R24") (pin "1") (pinfunction "1_1") (pintype "passive"))
      (node (ref "U5") (pin "C1") (pinfunction "VBAT_C1") (pintype "passive"))
      (node (ref "U5") (pin "C5") (pinfunction "VDD_C5") (pintype "passive"))
      (node (ref "U5") (pin "C7") (pinfunction "VDD_C7") (pintype "passive"))
      (node (ref "U5") (pin "C8") (pinfunction "VDD_C8") (pintype "passive"))
      (node (ref "U5") (pin "C9") (pinfunction "VDD_C9") (pintype "passive"))
      (node (ref "U5") (pin "F3") (pinfunction "VDD_F3") (pintype "passive"))
      (node (ref "U5") (pin "G13") (pinfunction "VDD_G13") (pintype "passive"))
      (node (ref "U5") (pin "G3") (pinfunction "VDD_G3") (pintype "passive"))
      (node (ref "U5") (pin "H13") (pinfunction "VDD_H13") (pintype "passive"))
      (node (ref "U5") (pin "J12") (pinfunction "VDD_J12") (pintype "passive"))
      (node (ref "U5") (pin "J13") (pinfunction "VDD_J13") (pintype "passive"))
      (node (ref "U5") (pin "K4") (pinfunction "VDD_K4") (pintype "passive"))
      (node (ref "U5") (pin "N10") (pinfunction "VDD_N10") (pintype "passive"))
      (node (ref "U5") (pin "N8") (pinfunction "VDD_N8") (pintype "passive"))
      (node (ref "U5") (pin "N9") (pinfunction "VDD_N9") (pintype "passive"))
      (node (ref "U5") (pin "P1") (pinfunction "VREF+_P1") (pintype "passive"))
      (node (ref "U5") (pin "R1") (pinfunction "VDDA_R1") (pintype "passive"))
      (node (ref "U7") (pin "5") (pinfunction "Vout_5") (pintype "passive"))
      (node (ref "X1") (pin "4") (pinfunction "VDD_4") (pintype "passive"))
    )
    (net (code "27") (name "5V") (class "Default")
      (node (ref "R12") (pin "1") (pinfunction "1_1") (pintype "passive"))
    )
    (net (code "28") (name "5V_USB_CHGR") (class "Default")
      (node (ref "C11") (pin "2") (pinfunction "2_2") (pintype "passive"))
      (node (ref "C2") (pin "2") (pinfunction "2_2") (pintype "passive"))
      (node (ref "CN1") (pin "1") (pinfunction "VBUS_1") (pintype "passive"))
      (node (ref "D1") (pin "1") (pinfunction "A_1") (pintype "passive"))
      (node (ref "R1") (pin "2") (pinfunction "2_2") (pintype "passive"))
      (node (ref "R6") (pin "2") (pinfunction "2_2") (pintype "passive"))
      (node (ref "U3") (pin "1") (pinfunction "IO1_1") (pintype "passive"))
      (node (ref "U4") (pin "5") (pinfunction "IN_5") (pintype "passive"))
    )
    (net (code "29") (name "5V_USB_STLK") (class "Default")
      (node (ref "C5") (pin "2") (pinfunction "2_2") (pintype "passive"))
      (node (ref "U4") (pin "1") (pinfunction "OUT_1") (pintype "passive"))
    )
    (net (code "30") (name "5V_VIN") (class "Default")
      (node (ref "D3") (pin "1") (pinfunction "A_1") (pintype "passive"))
    )
    (net (code "31") (name "E5V") (class "Default")
      (node (ref "D2") (pin "1") (pinfunction "A_1") (pintype "passive"))
    )
    (net (code "32") (name "GND") (class "Default")
      (node (ref "C1") (pin "1") (pinfunction "1_1") (pintype "passive"))
      (node (ref "C10") (pin "1") (pinfunction "1_1") (pintype "passive"))
      (node (ref "C11") (pin "1") (pinfunction "1_1") (pintype "passive"))
      (node (ref "C12") (pin "1") (pinfunction "1_1") (pintype "passive"))
      (node (ref "C13") (pin "1") (pinfunction "1_1") (pintype "passive"))
      (node (ref "C14") (pin "1") (pinfunction "1_1") (pintype "passive"))
      (node (ref "C15") (pin "1") (pinfunction "1_1") (pintype "passive"))
      (node (ref "C16") (pin "1") (pinfunction "1_1") (pintype "passive"))
      (node (ref "C17") (pin "1") (pinfunction "1_1") (pintype "passive"))
      (node (ref "C18") (pin "1") (pinfunction "1_1") (pintype "passive"))
      (node (ref "C19") (pin "1") (pinfunction "1_1") (pintype "passive"))
      (node (ref "C2") (pin "1") (pinfunction "1_1") (pintype "passive"))
      (node (ref "C20") (pin "1") (pinfunction "1_1") (pintype "passive"))
      (node (ref "C21") (pin "1") (pinfunction "1_1") (pintype "passive"))
      (node (ref "C22") (pin "1") (pinfunction "1_1") (pintype "passive"))
      (node (ref "C23") (pin "1") (pinfunction "1_1") (pintype "passive"))
      (node (ref "C24") (pin "1") (pinfunction "1_1") (pintype "passive"))
      (node (ref "C25") (pin "1") (pinfunction "1_1") (pintype "passive"))
      (node (ref "C26") (pin "1") (pinfunction "1_1") (pintype "passive"))
      (node (ref "C27") (pin "1") (pinfunction "1_1") (pintype "passive"))
      (node (ref "C28") (pin "1") (pinfunction "1_1") (pintype "passive"))
      (node (ref "C29") (pin "1") (pinfunction "1_1") (pintype "passive"))
      (node (ref "C3") (pin "1") (pinfunction "1_1") (pintype "passive"))
      (node (ref "C30") (pin "1") (pinfunction "1_1") (pintype "passive"))
      (node (ref "C31") (pin "1") (pinfunction "1_1") (pintype "passive"))
      (node (ref "C32") (pin "1") (pinfunction "1_1") (pintype "passive"))
      (node (ref "C33") (pin "1") (pinfunction "1_1") (pintype "passive"))
      (node (ref "C4") (pin "1") (pinfunction "1_1") (pintype "passive"))
      (node (ref "C5") (pin "1") (pinfunction "1_1") (pintype "passive"))
      (node (ref "C6") (pin "1") (pinfunction "1_1") (pintype "passive"))
      (node (ref "C7") (pin "1") (pinfunction "1_1") (pintype "passive"))
      (node (ref "C8") (pin "1") (pinfunction "1_1") (pintype "passive"))
      (node (ref "C9") (pin "1") (pinfunction "1_1") (pintype "passive"))
      (node (ref "CN1") (pin "10") (pinfunction "EXP_10") (pintype "passive"))
      (node (ref "CN1") (pin "11") (pinfunction "EXP_11") (pintype "passive"))
      (node (ref "CN1") (pin "5") (pinfunction "GND_5") (pintype "passive"))
      (node (ref "CN1") (pin "6") (pinfunction "Shield_6") (pintype "passive"))
      (node (ref "CN1") (pin "7") (pinfunction "Shield_7") (pintype "passive"))
      (node (ref "CN1") (pin "8") (pinfunction "Shield_8") (pintype "passive"))
      (node (ref "CN1") (pin "9") (pinfunction "Shield_9") (pintype "passive"))
      (node (ref "CN11") (pin "1") (pinfunction "COMMON_1") (pintype "passive"))
      (node (ref "CN11") (pin "2") (pinfunction "NO_2") (pintype "passive"))
      (node (ref "CN12") (pin "1") (pinfunction "COMMON_1") (pintype "passive"))
      (node (ref "CN12") (pin "2") (pinfunction "NO_2") (pintype "passive"))
      (node (ref "CN2") (pin "3") (pinfunction "3_3") (pintype "passive"))
      (node (ref "CN4") (pin "5") (pinfunction "5_5") (pintype "passive"))
      (node (ref "CN4") (pin "7") (pinfunction "7_7") (pintype "passive"))
      (node (ref "JP1") (pin "1") (pinfunction "COMMON_1") (pintype "passive"))
      (node (ref "LD1") (pin "1") (pinfunction "RED_cathode_1") (pintype "passive"))
      (node (ref "R11") (pin "1") (pinfunction "1_1") (pintype "passive"))
      (node (ref "R15") (pin "1") (pinfunction "1_1") (pintype "passive"))
      (node (ref "R16") (pin "2") (pinfunction "2_2") (pintype "passive"))
      (node (ref "R17") (pin "1") (pinfunction "1_1") (pintype "passive"))
      (node (ref "R21") (pin "1") (pinfunction "1_1") (pintype "passive"))
      (node (ref "R5") (pin "1") (pinfunction "1_1") (pintype "passive"))
      (node (ref "R8") (pin "2") (pinfunction "2_2") (pintype "passive"))
      (node (ref "U1") (pin "2") (pinfunction "GND_2") (pintype "passive"))
      (node (ref "U2") (pin "3") (pinfunction "GND_3") (pintype "passive"))
      (node (ref "U3") (pin "2") (pinfunction "GND_2") (pintype "passive"))
      (node (ref "U4") (pin "2") (pinfunction "GND_2") (pintype "passive"))
      (node (ref "U5") (pin "D5") (pinfunction "VSS_D5") (pintype "passive"))
      (node (ref "U5") (pin "D7") (pinfunction "VSS_D7") (pintype "passive"))
      (node (ref "U5") (pin "D8") (pinfunction "VSS_D8") (pintype "passive"))
      (node (ref "U5") (pin "D9") (pinfunction "VSS_D9") (pintype "passive"))
      (node (ref "U5") (pin "F10") (pinfunction "VSS_F10") (pintype "passive"))
      (node (ref "U5") (pin "F12") (pinfunction "VSS_F12") (pintype "passive"))
      (node (ref "U5") (pin "F2") (pinfunction "VSS_F2") (pintype "passive"))
      (node (ref "U5") (pin "F6") (pinfunction "VSS_F6") (pintype "passive"))
      (node (ref "U5") (pin "F7") (pinfunction "VSS_F7") (pintype "passive"))
      (node (ref "U5") (pin "F8") (pinfunction "VSS_F8") (pintype "passive"))
      (node (ref "U5") (pin "F9") (pinfunction "VSS_F9") (pintype "passive"))
      (node (ref "U5") (pin "G10") (pinfunction "VSS_G10") (pintype "passive"))
      (node (ref "U5") (pin "G12") (pinfunction "VSS_G12") (pintype "passive"))
      (node (ref "U5") (pin "G2") (pinfunction "VSS_G2") (pintype "passive"))
      (node (ref "U5") (pin "G6") (pinfunction "VSS_G6") (pintype "passive"))
      (node (ref "U5") (pin "G7") (pinfunction "VSS_G7") (pintype "passive"))
      (node (ref "U5") (pin "G8") (pinfunction "VSS_G8") (pintype "passive"))
      (node (ref "U5") (pin "G9") (pinfunction "VSS_G9") (pintype "passive"))
      (node (ref "U5") (pin "H10") (pinfunction "VSS_H10") (pintype "passive"))
      (node (ref "U5") (pin "H12") (pinfunction "VSS_H12") (pintype "passive"))
      (node (ref "U5") (pin "H6") (pinfunction "VSS_H6") (pintype "passive"))
      (node (ref "U5") (pin "H7") (pinfunction "VSS_H7") (pintype "passive"))
      (node (ref "U5") (pin "H8") (pinfunction "VSS_H8") (pintype "passive"))
      (node (ref "U5") (pin "H9") (pinfunction "VSS_H9") (pintype "passive"))
      (node (ref "U5") (pin "J10") (pinfunction "VSS_J10") (pintype "passive"))
      (node (ref "U5") (pin "J6") (pinfunction "VSS_J6") (pintype "passive"))
      (node (ref "U5") (pin "J7") (pinfunction "VSS_J7") (pintype "passive"))
      (node (ref "U5") (pin "J8") (pinfunction "VSS_J8") (pintype "passive"))
      (node (ref "U5") (pin "J9") (pinfunction "VSS_J9") (pintype "passive"))
      (node (ref "U5") (pin "K10") (pinfunction "VSS_K10") (pintype "passive"))
      (node (ref "U5") (pin "K6") (pinfunction "VSS_K6") (pintype "passive"))
      (node (ref "U5") (pin "K7") (pinfunction "VSS_K7") (pintype "passive"))
      (node (ref "U5") (pin "K8") (pinfunction "VSS_K8") (pintype "passive"))
      (node (ref "U5") (pin "K9") (pinfunction "VSS_K9") (pintype "passive"))
      (node (ref "U5") (pin "M1") (pinfunction "VSSA_M1") (pintype "passive"))
      (node (ref "U5") (pin "M8") (pinfunction "VSS_M8") (pintype "passive"))
      (node (ref "U5") (pin "M9") (pinfunction "VSS_M9") (pintype "passive"))
      (node (ref "U5") (pin "N1") (pinfunction "VREF-_N1") (pintype "passive"))
      (node (ref "U6") (pin "2") (pinfunction "GND_2") (pintype "passive"))
      (node (ref "U7") (pin "2") (pinfunction "GND_2") (pintype "passive"))
      (node (ref "U8") (pin "2") (pinfunction "GND_2") (pintype "passive"))
      (node (ref "X1") (pin "2") (pinfunction "GND_2") (pintype "passive"))
    )
    (net (code "33") (name "Net-(D1-K)") (class "Default")
      (node (ref "C19") (pin "2") (pinfunction "2_2") (pintype "passive"))
      (node (ref "C20") (pin "2") (pinfunction "2_2") (pintype "passive"))
      (node (ref "D1") (pin "2") (pinfunction "K_2") (pintype "passive"))
      (node (ref "D2") (pin "2") (pinfunction "K_2") (pintype "passive"))
      (node (ref "D3") (pin "2") (pinfunction "K_2") (pintype "passive"))
      (node (ref "U7") (pin "1") (pinfunction "Vin_1") (pintype "passive"))
      (node (ref "U7") (pin "3") (pinfunction "CE_3") (pintype "passive"))
    )
    (net (code "34") (name "Net-(JP1-NO)") (class "Default")
      (node (ref "C1") (pin "2") (pinfunction "2_2") (pintype "passive"))
      (node (ref "JP1") (pin "2") (pinfunction "NO_2") (pintype "passive"))
      (node (ref "U5") (pin "J1") (pinfunction "NRST_J1") (pintype "passive"))
    )
    (net (code "35") (name "Net-(JP3-NO)") (class "Default")
      (node (ref "JP3") (pin "2") (pinfunction "NO_2") (pintype "passive"))
      (node (ref "R18") (pin "1") (pinfunction "1_1") (pintype "passive"))
    )
    (net (code "36") (name "Net-(LD1-Red_anode)") (class "Default")
      (node (ref "LD1") (pin "2") (pinfunction "Red_anode_2") (pintype "passive"))
      (node (ref "R3") (pin "1") (pinfunction "1_1") (pintype "passive"))
    )
    (net (code "37") (name "Net-(LD1-YellowGreen_cathode)") (class "Default")
      (node (ref "LD1") (pin "3") (pinfunction "YellowGreen_cathode_3") (pintype "passive"))
      (node (ref "R2") (pin "1") (pinfunction "1_1") (pintype "passive"))
    )
    (net (code "38") (name "Net-(LD4-Pad1)") (class "Default")
      (node (ref "LD4") (pin "1") (pintype "passive"))
      (node (ref "R1") (pin "1") (pinfunction "1_1") (pintype "passive"))
    )
    (net (code "39") (name "Net-(U4-~{FAULT})") (class "Default")
      (node (ref "LD4") (pin "2") (pintype "passive"))
      (node (ref "R6") (pin "1") (pinfunction "1_1") (pintype "passive"))
      (node (ref "U4") (pin "3") (pinfunction "~{FAULT}_3") (pintype "passive"))
    )
    (net (code "40") (name "Net-(U5A-BOOT0)") (class "Default")
      (node (ref "R17") (pin "2") (pinfunction "2_2") (pintype "passive"))
      (node (ref "U5") (pin "D6") (pinfunction "BOOT0_D6") (pintype "passive"))
    )
    (net (code "41") (name "Net-(U5A-OSC_IN{slash}PH0)") (class "Default")
      (node (ref "R20") (pin "2") (pinfunction "2_2") (pintype "passive"))
      (node (ref "U5") (pin "G1") (pinfunction "OSC_IN/PH0_G1") (pintype "passive"))
    )
    (net (code "42") (name "Net-(U5A-PDR_ON)") (class "Default")
      (node (ref "R14") (pin "2") (pinfunction "2_2") (pintype "passive"))
      (node (ref "U5") (pin "C6") (pinfunction "PDR_ON_C6") (pintype "passive"))
    )
    (net (code "43") (name "Net-(U5A-REXT_OTGPHY)") (class "Default")
      (node (ref "R5") (pin "2") (pinfunction "2_2") (pintype "passive"))
      (node (ref "U5") (pin "J15") (pinfunction "REXT_OTGPHY_J15") (pintype "passive"))
    )
    (net (code "44") (name "Net-(U5A-STLK_MCO{slash}PA8)") (class "Default")
      (node (ref "R4") (pin "1") (pinfunction "1_1") (pintype "passive"))
      (node (ref "U5") (pin "F15") (pinfunction "STLK_MCO/PA8_F15") (pintype "passive"))
    )
    (net (code "45") (name "Net-(U5A-T_VCC_AIN{slash}PA0)") (class "Default")
      (node (ref "R16") (pin "1") (pinfunction "1_1") (pintype "passive"))
      (node (ref "R19") (pin "1") (pinfunction "1_1") (pintype "passive"))
      (node (ref "U5") (pin "N3") (pinfunction "T_VCC_AIN/PA0_N3") (pintype "passive"))
    )
    (net (code "46") (name "Net-(U5A-V12_OTGPHY)") (class "Default")
      (node (ref "C4") (pin "2") (pinfunction "2_2") (pintype "passive"))
      (node (ref "U5") (pin "J14") (pinfunction "V12_OTGPHY_J14") (pintype "passive"))
    )
    (net (code "47") (name "Net-(U5B-BYPASS-REG)") (class "Default")
      (node (ref "R21") (pin "2") (pinfunction "2_2") (pintype "passive"))
      (node (ref "U5") (pin "L4") (pinfunction "BYPASS-REG_L4") (pintype "passive"))
    )
    (net (code "48") (name "Net-(U5B-VCAP1)") (class "Default")
      (node (ref "C12") (pin "2") (pinfunction "2_2") (pintype "passive"))
      (node (ref "U5") (pin "M10") (pinfunction "VCAP1_M10") (pintype "passive"))
    )
    (net (code "49") (name "Net-(U5B-VCAP2)") (class "Default")
      (node (ref "C10") (pin "2") (pinfunction "2_2") (pintype "passive"))
      (node (ref "U5") (pin "F13") (pinfunction "VCAP2_F13") (pintype "passive"))
    )
    (net (code "50") (name "Net-(U7-BYPASS)") (class "Default")
      (node (ref "C30") (pin "2") (pinfunction "2_2") (pintype "passive"))
      (node (ref "U7") (pin "4") (pinfunction "BYPASS_4") (pintype "passive"))
    )
    (net (code "51") (name "Net-(X1-EN)") (class "Default")
      (node (ref "R24") (pin "2") (pinfunction "2_2") (pintype "passive"))
      (node (ref "X1") (pin "1") (pinfunction "EN_1") (pintype "passive"))
    )
    (net (code "52") (name "Net-(X1-OUT)") (class "Default")
      (node (ref "R20") (pin "1") (pinfunction "1_1") (pintype "passive"))
      (node (ref "X1") (pin "3") (pinfunction "OUT_3") (pintype "passive"))
    )
    (net (code "53") (name "unconnected-(CN1-ID-Pad4)") (class "Default")
      (node (ref "CN1") (pin "4") (pinfunction "ID_4") (pintype "passive+no_connect"))
    )
    (net (code "54") (name "unconnected-(CN4-Pad1)") (class "Default")
      (node (ref "CN4") (pin "1") (pinfunction "1_1") (pintype "passive+no_connect"))
    )
    (net (code "55") (name "unconnected-(CN4-Pad2)") (class "Default")
      (node (ref "CN4") (pin "2") (pinfunction "2_2") (pintype "passive+no_connect"))
    )
    (net (code "56") (name "unconnected-(CN4-Pad9)") (class "Default")
      (node (ref "CN4") (pin "9") (pinfunction "9_9") (pintype "passive+no_connect"))
    )
    (net (code "57") (name "unconnected-(U2-NC-Pad4)") (class "Default")
      (node (ref "U2") (pin "4") (pinfunction "NC_4") (pintype "passive+no_connect"))
    )
    (net (code "58") (name "unconnected-(U5A-HW_TYP_0{slash}PI4-PadD4)") (class "Default")
      (node (ref "U5") (pin "D4") (pinfunction "HW_TYP_0/PI4_D4") (pintype "passive+no_connect"))
    )
    (net (code "59") (name "unconnected-(U5A-HW_TYP_1{slash}PI5-PadC4)") (class "Default")
      (node (ref "U5") (pin "C4") (pinfunction "HW_TYP_1/PI5_C4") (pintype "passive+no_connect"))
    )
    (net (code "60") (name "unconnected-(U5A-OSC_OUT{slash}PH1-PadH1)") (class "Default")
      (node (ref "U5") (pin "H1") (pinfunction "OSC_OUT/PH1_H1") (pintype "passive+no_connect"))
    )
    (net (code "61") (name "unconnected-(U5A-T_SW_DIR{slash}PA7-PadR3)") (class "Default")
      (node (ref "U5") (pin "R3") (pinfunction "T_SW_DIR/PA7_R3") (pintype "passive+no_connect"))
    )
  )
)
